# Main.net
KiCad netlist of a schematic drawn in Altium Designer
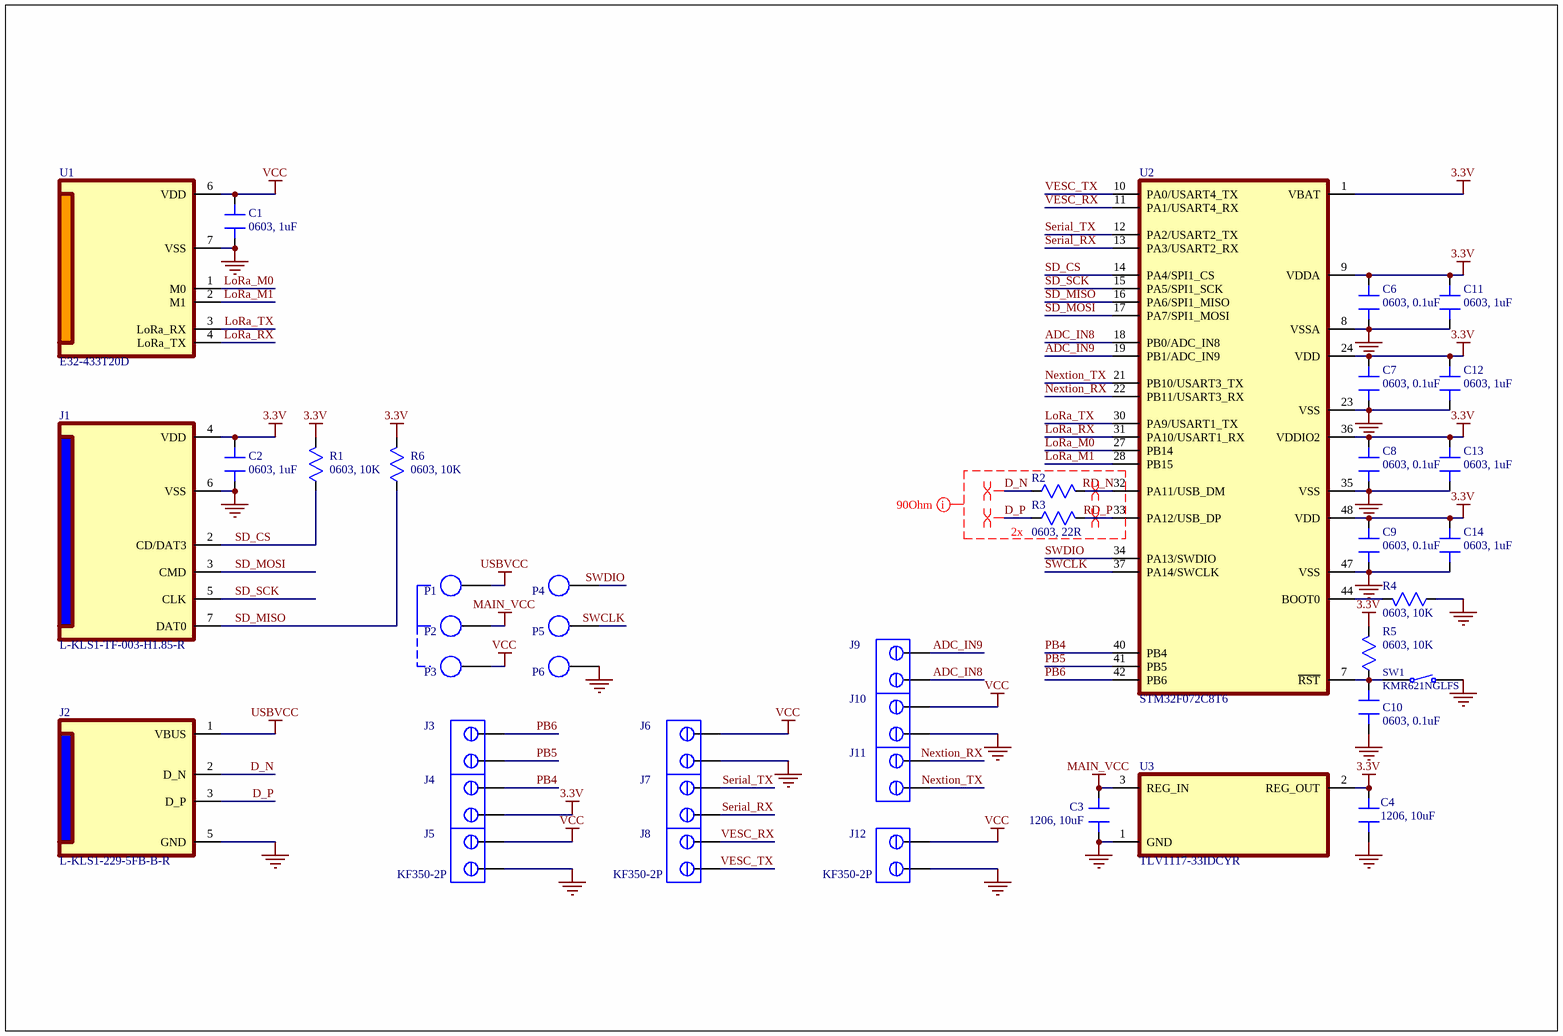
[diagram p0: Main.SchDoc]

(export (version "E")
  (design (tool "Eeschema 10.0.6"))
  (components
    (comp (ref "C1")
      (value "0603, 1uF")
      (footprint "CAP 0603_1608")
      (libsource (lib "Passives") (part "0603 Kapasitör"))
    )
    (comp (ref "C2")
      (value "0603, 1uF")
      (footprint "CAP 0603_1608")
      (libsource (lib "Passives") (part "0603 Kapasitör"))
    )
    (comp (ref "C3")
      (value "1206, 10uF")
      (footprint "CAP 1206_3216")
      (libsource (lib "Passives") (part "1206 Kapasitör"))
    )
    (comp (ref "C4")
      (value "1206, 10uF")
      (footprint "CAP 1206_3216")
      (libsource (lib "Passives") (part "1206 Kapasitör"))
    )
    (comp (ref "C6")
      (value "0603, 0.1uF")
      (footprint "CAP 0603_1608")
      (libsource (lib "Passives") (part "0603 Kapasitör"))
    )
    (comp (ref "C7")
      (value "0603, 0.1uF")
      (footprint "CAP 0603_1608")
      (libsource (lib "Passives") (part "0603 Kapasitör"))
    )
    (comp (ref "C8")
      (value "0603, 0.1uF")
      (footprint "CAP 0603_1608")
      (libsource (lib "Passives") (part "0603 Kapasitör"))
    )
    (comp (ref "C9")
      (value "0603, 0.1uF")
      (footprint "CAP 0603_1608")
      (libsource (lib "Passives") (part "0603 Kapasitör"))
    )
    (comp (ref "C10")
      (value "0603, 0.1uF")
      (footprint "CAP 0603_1608")
      (libsource (lib "Passives") (part "0603 Kapasitör"))
    )
    (comp (ref "C11")
      (value "0603, 1uF")
      (footprint "CAP 0603_1608")
      (libsource (lib "Passives") (part "0603 Kapasitör"))
    )
    (comp (ref "C12")
      (value "0603, 1uF")
      (footprint "CAP 0603_1608")
      (libsource (lib "Passives") (part "0603 Kapasitör"))
    )
    (comp (ref "C13")
      (value "0603, 1uF")
      (footprint "CAP 0603_1608")
      (libsource (lib "Passives") (part "0603 Kapasitör"))
    )
    (comp (ref "C14")
      (value "0603, 1uF")
      (footprint "CAP 0603_1608")
      (libsource (lib "Passives") (part "0603 Kapasitör"))
    )
    (comp (ref "J1")
      (value "L-KLS1-TF-003-H1.85-R")
      (footprint "L-KLS1-TF-003-H1.85-R")
      (libsource (lib "L-KLS1-TF-003-H1.85-R") (part "L-KLS1-TF-003-H1.85-R"))
    )
    (comp (ref "J2")
      (value "L-KLS1-229-5FB-B-R")
      (footprint "L-KLS1-229-5FB-B-R")
      (libsource (lib "L-KLS1-229-5FB-B-R") (part "L-KLS1-229-5FB-B-R"))
    )
    (comp (ref "J3") (value "KF350-2P") (footprint "KF350-2P") (libsource (lib "KF350") (part "KF350-2P")))
    (comp (ref "J4") (value "KF350-2P") (footprint "KF350-2P") (libsource (lib "KF350") (part "KF350-2P")))
    (comp (ref "J5") (value "KF350-2P") (footprint "KF350-2P") (libsource (lib "KF350") (part "KF350-2P")))
    (comp (ref "J6") (value "KF350-2P") (footprint "KF350-2P") (libsource (lib "KF350") (part "KF350-2P")))
    (comp (ref "J7") (value "KF350-2P") (footprint "KF350-2P") (libsource (lib "KF350") (part "KF350-2P")))
    (comp (ref "J8") (value "KF350-2P") (footprint "KF350-2P") (libsource (lib "KF350") (part "KF350-2P")))
    (comp (ref "J9") (value "KF350-2P") (footprint "KF350-2P") (libsource (lib "KF350") (part "KF350-2P")))
    (comp (ref "J10") (value "KF350-2P") (footprint "KF350-2P") (libsource (lib "KF350") (part "KF350-2P")))
    (comp (ref "J11") (value "KF350-2P") (footprint "KF350-2P") (libsource (lib "KF350") (part "KF350-2P")))
    (comp (ref "J12") (value "KF350-2P") (footprint "KF350-2P") (libsource (lib "KF350") (part "KF350-2P")))
    (comp (ref "P1") (value "Pad") (footprint "PAD") (libsource (lib "Passives") (part "Pad")))
    (comp (ref "P2") (value "Pad") (footprint "PAD") (libsource (lib "Passives") (part "Pad")))
    (comp (ref "P3") (value "Pad") (footprint "PAD") (libsource (lib "Passives") (part "Pad")))
    (comp (ref "P4") (value "Pad") (footprint "PAD") (libsource (lib "Passives") (part "Pad")))
    (comp (ref "P5") (value "Pad") (footprint "PAD") (libsource (lib "Passives") (part "Pad")))
    (comp (ref "P6") (value "Pad") (footprint "PAD") (libsource (lib "Passives") (part "Pad")))
    (comp (ref "R1")
      (value "0603, 10K")
      (footprint "RES 0603_1608")
      (libsource (lib "Passives") (part "0603 Direnç"))
    )
    (comp (ref "R2")
      (value "0603, ?R/K")
      (footprint "RES 0603_1608")
      (libsource (lib "Passives") (part "0603 Direnç"))
    )
    (comp (ref "R3")
      (value "0603, 22R")
      (footprint "RES 0603_1608")
      (libsource (lib "Passives") (part "0603 Direnç"))
    )
    (comp (ref "R4")
      (value "0603, 10K")
      (footprint "RES 0603_1608")
      (libsource (lib "Passives") (part "0603 Direnç"))
    )
    (comp (ref "R5")
      (value "0603, 10K")
      (footprint "RES 0603_1608")
      (libsource (lib "Passives") (part "0603 Direnç"))
    )
    (comp (ref "R6")
      (value "0603, 10K")
      (footprint "RES 0603_1608")
      (libsource (lib "Passives") (part "0603 Direnç"))
    )
    (comp (ref "SW1")
      (value "KMR621NGLFS")
      (footprint "SW_KMR621NGLFS")
      (libsource (lib "KMR621NGLFS") (part "KMR621NGLFS"))
    )
    (comp (ref "U1")
      (value "E32-433T20D")
      (footprint "E32-433T20D")
      (libsource (lib "E32-433T20D") (part "E32-433T20D"))
    )
    (comp (ref "U2")
      (value "STM32F072C8T6")
      (footprint "STM32F072C8T6")
      (libsource (lib "STM32F072C8T6") (part "STM32F072C8T6"))
    )
    (comp (ref "U3")
      (value "TLV1117-33IDCYR")
      (footprint "SOT230P700X180-4N")
      (libsource (lib "TLV1117-33IDCYR") (part "TLV1117-33IDCYR"))
    )
  )
  (nets
    (net (code "1") (name "/ADC_IN8") (class "Default")
      (node (ref "J9") (pin "2") (pinfunction "2_2") (pintype "passive"))
      (node (ref "U2") (pin "18") (pinfunction "PB0/ADC_IN8_18") (pintype "passive"))
    )
    (net (code "2") (name "/ADC_IN9") (class "Default")
      (node (ref "J9") (pin "1") (pinfunction "1_1") (pintype "passive"))
      (node (ref "U2") (pin "19") (pinfunction "PB1/ADC_IN9_19") (pintype "passive"))
    )
    (net (code "3") (name "/D_N") (class "Default")
      (node (ref "J2") (pin "2") (pinfunction "D_N_2") (pintype "passive"))
      (node (ref "R2") (pin "2") (pinfunction "2_2") (pintype "passive"))
    )
    (net (code "4") (name "/D_P") (class "Default")
      (node (ref "J2") (pin "3") (pinfunction "D_P_3") (pintype "passive"))
      (node (ref "R3") (pin "2") (pinfunction "2_2") (pintype "passive"))
    )
    (net (code "5") (name "/LoRa_M0") (class "Default")
      (node (ref "U1") (pin "1") (pinfunction "M0_1") (pintype "passive"))
      (node (ref "U2") (pin "27") (pinfunction "PB14_27") (pintype "passive"))
    )
    (net (code "6") (name "/LoRa_M1") (class "Default")
      (node (ref "U1") (pin "2") (pinfunction "M1_2") (pintype "passive"))
      (node (ref "U2") (pin "28") (pinfunction "PB15_28") (pintype "passive"))
    )
    (net (code "7") (name "/LoRa_RX") (class "Default")
      (node (ref "U1") (pin "4") (pinfunction "LoRa_TX_4") (pintype "passive"))
      (node (ref "U2") (pin "31") (pinfunction "PA10/USART1_RX_31") (pintype "passive"))
    )
    (net (code "8") (name "/LoRa_TX") (class "Default")
      (node (ref "U1") (pin "3") (pinfunction "LoRa_RX_3") (pintype "passive"))
      (node (ref "U2") (pin "30") (pinfunction "PA9/USART1_TX_30") (pintype "passive"))
    )
    (net (code "9") (name "/Nextion_RX") (class "Default")
      (node (ref "J11") (pin "1") (pinfunction "1_1") (pintype "passive"))
      (node (ref "U2") (pin "22") (pinfunction "PB11/USART3_RX_22") (pintype "passive"))
    )
    (net (code "10") (name "/Nextion_TX") (class "Default")
      (node (ref "J11") (pin "2") (pinfunction "2_2") (pintype "passive"))
      (node (ref "U2") (pin "21") (pinfunction "PB10/USART3_TX_21") (pintype "passive"))
    )
    (net (code "11") (name "/PB4") (class "Default")
      (node (ref "J4") (pin "1") (pinfunction "1_1") (pintype "passive"))
      (node (ref "U2") (pin "40") (pinfunction "PB4_40") (pintype "passive"))
    )
    (net (code "12") (name "/PB5") (class "Default")
      (node (ref "J3") (pin "2") (pinfunction "2_2") (pintype "passive"))
      (node (ref "U2") (pin "41") (pinfunction "PB5_41") (pintype "passive"))
    )
    (net (code "13") (name "/PB6") (class "Default")
      (node (ref "J3") (pin "1") (pinfunction "1_1") (pintype "passive"))
      (node (ref "U2") (pin "42") (pinfunction "PB6_42") (pintype "passive"))
    )
    (net (code "14") (name "/RD_N") (class "Default")
      (node (ref "R2") (pin "1") (pinfunction "1_1") (pintype "passive"))
      (node (ref "U2") (pin "32") (pinfunction "PA11/USB_DM_32") (pintype "passive"))
    )
    (net (code "15") (name "/RD_P") (class "Default")
      (node (ref "R3") (pin "1") (pinfunction "1_1") (pintype "passive"))
      (node (ref "U2") (pin "33") (pinfunction "PA12/USB_DP_33") (pintype "passive"))
    )
    (net (code "16") (name "/SD_CS") (class "Default")
      (node (ref "J1") (pin "2") (pinfunction "CD/DAT3_2") (pintype "passive"))
      (node (ref "R1") (pin "2") (pinfunction "2_2") (pintype "passive"))
      (node (ref "U2") (pin "14") (pinfunction "PA4/SPI1_CS_14") (pintype "passive"))
    )
    (net (code "17") (name "/SD_MISO") (class "Default")
      (node (ref "J1") (pin "7") (pinfunction "DAT0_7") (pintype "passive"))
      (node (ref "R6") (pin "2") (pinfunction "2_2") (pintype "passive"))
      (node (ref "U2") (pin "16") (pinfunction "PA6/SPI1_MISO_16") (pintype "passive"))
    )
    (net (code "18") (name "/SD_MOSI") (class "Default")
      (node (ref "J1") (pin "3") (pinfunction "CMD_3") (pintype "passive"))
      (node (ref "U2") (pin "17") (pinfunction "PA7/SPI1_MOSI_17") (pintype "passive"))
    )
    (net (code "19") (name "/SD_SCK") (class "Default")
      (node (ref "J1") (pin "5") (pinfunction "CLK_5") (pintype "passive"))
      (node (ref "U2") (pin "15") (pinfunction "PA5/SPI1_SCK_15") (pintype "passive"))
    )
    (net (code "20") (name "/SWCLK") (class "Default")
      (node (ref "P5") (pin "1") (pinfunction "1_1") (pintype "passive"))
      (node (ref "U2") (pin "37") (pinfunction "PA14/SWCLK_37") (pintype "passive"))
    )
    (net (code "21") (name "/SWDIO") (class "Default")
      (node (ref "P4") (pin "1") (pinfunction "1_1") (pintype "passive"))
      (node (ref "U2") (pin "34") (pinfunction "PA13/SWDIO_34") (pintype "passive"))
    )
    (net (code "22") (name "/Serial_RX") (class "Default")
      (node (ref "J7") (pin "2") (pinfunction "2_2") (pintype "passive"))
      (node (ref "U2") (pin "13") (pinfunction "PA3/USART2_RX_13") (pintype "passive"))
    )
    (net (code "23") (name "/Serial_TX") (class "Default")
      (node (ref "J7") (pin "1") (pinfunction "1_1") (pintype "passive"))
      (node (ref "U2") (pin "12") (pinfunction "PA2/USART2_TX_12") (pintype "passive"))
    )
    (net (code "24") (name "/VESC_RX") (class "Default")
      (node (ref "J8") (pin "1") (pinfunction "1_1") (pintype "passive"))
      (node (ref "U2") (pin "11") (pinfunction "PA1/USART4_RX_11") (pintype "passive"))
    )
    (net (code "25") (name "/VESC_TX") (class "Default")
      (node (ref "J8") (pin "2") (pinfunction "2_2") (pintype "passive"))
      (node (ref "U2") (pin "10") (pinfunction "PA0/USART4_TX_10") (pintype "passive"))
    )
    (net (code "26") (name "3.3V") (class "Default")
      (node (ref "C11") (pin "2") (pinfunction "2_2") (pintype "passive"))
      (node (ref "C12") (pin "2") (pinfunction "2_2") (pintype "passive"))
      (node (ref "C13") (pin "2") (pinfunction "2_2") (pintype "passive"))
      (node (ref "C14") (pin "2") (pinfunction "2_2") (pintype "passive"))
      (node (ref "C2") (pin "2") (pinfunction "2_2") (pintype "passive"))
      (node (ref "C4") (pin "2") (pinfunction "2_2") (pintype "passive"))
      (node (ref "C6") (pin "2") (pinfunction "2_2") (pintype "passive"))
      (node (ref "C7") (pin "2") (pinfunction "2_2") (pintype "passive"))
      (node (ref "C8") (pin "2") (pinfunction "2_2") (pintype "passive"))
      (node (ref "C9") (pin "2") (pinfunction "2_2") (pintype "passive"))
      (node (ref "J1") (pin "4") (pinfunction "VDD_4") (pintype "passive"))
      (node (ref "J4") (pin "2") (pinfunction "2_2") (pintype "passive"))
      (node (ref "R1") (pin "1") (pinfunction "1_1") (pintype "passive"))
      (node (ref "R5") (pin "1") (pinfunction "1_1") (pintype "passive"))
      (node (ref "R6") (pin "1") (pinfunction "1_1") (pintype "passive"))
      (node (ref "U2") (pin "1") (pinfunction "VBAT_1") (pintype "passive"))
      (node (ref "U2") (pin "24") (pinfunction "VDD_24") (pintype "passive"))
      (node (ref "U2") (pin "36") (pinfunction "VDDIO2_36") (pintype "passive"))
      (node (ref "U2") (pin "48") (pinfunction "VDD_48") (pintype "passive"))
      (node (ref "U2") (pin "9") (pinfunction "VDDA_9") (pintype "passive"))
      (node (ref "U3") (pin "2") (pinfunction "REG_OUT_2") (pintype "passive"))
    )
    (net (code "27") (name "GND") (class "Default")
      (node (ref "C1") (pin "1") (pinfunction "1_1") (pintype "passive"))
      (node (ref "C10") (pin "1") (pinfunction "1_1") (pintype "passive"))
      (node (ref "C11") (pin "1") (pinfunction "1_1") (pintype "passive"))
      (node (ref "C12") (pin "1") (pinfunction "1_1") (pintype "passive"))
      (node (ref "C13") (pin "1") (pinfunction "1_1") (pintype "passive"))
      (node (ref "C14") (pin "1") (pinfunction "1_1") (pintype "passive"))
      (node (ref "C2") (pin "1") (pinfunction "1_1") (pintype "passive"))
      (node (ref "C3") (pin "1") (pinfunction "1_1") (pintype "passive"))
      (node (ref "C4") (pin "1") (pinfunction "1_1") (pintype "passive"))
      (node (ref "C6") (pin "1") (pinfunction "1_1") (pintype "passive"))
      (node (ref "C7") (pin "1") (pinfunction "1_1") (pintype "passive"))
      (node (ref "C8") (pin "1") (pinfunction "1_1") (pintype "passive"))
      (node (ref "C9") (pin "1") (pinfunction "1_1") (pintype "passive"))
      (node (ref "J1") (pin "6") (pinfunction "VSS_6") (pintype "passive"))
      (node (ref "J10") (pin "2") (pinfunction "2_2") (pintype "passive"))
      (node (ref "J12") (pin "2") (pinfunction "2_2") (pintype "passive"))
      (node (ref "J2") (pin "5") (pinfunction "GND_5") (pintype "passive"))
      (node (ref "J5") (pin "2") (pinfunction "2_2") (pintype "passive"))
      (node (ref "J6") (pin "2") (pinfunction "2_2") (pintype "passive"))
      (node (ref "P6") (pin "1") (pinfunction "1_1") (pintype "passive"))
      (node (ref "R4") (pin "2") (pinfunction "2_2") (pintype "passive"))
      (node (ref "SW1") (pin "1") (pinfunction "1_1") (pintype "passive"))
      (node (ref "U1") (pin "7") (pinfunction "VSS_7") (pintype "passive"))
      (node (ref "U2") (pin "23") (pinfunction "VSS_23") (pintype "passive"))
      (node (ref "U2") (pin "35") (pinfunction "VSS_35") (pintype "passive"))
      (node (ref "U2") (pin "47") (pinfunction "VSS_47") (pintype "passive"))
      (node (ref "U2") (pin "8") (pinfunction "VSSA_8") (pintype "passive"))
      (node (ref "U3") (pin "1") (pinfunction "GND_1") (pintype "passive"))
    )
    (net (code "28") (name "MAIN_VCC") (class "Default")
      (node (ref "C3") (pin "2") (pinfunction "2_2") (pintype "passive"))
      (node (ref "P2") (pin "1") (pinfunction "1_1") (pintype "passive"))
      (node (ref "U3") (pin "3") (pinfunction "REG_IN_3") (pintype "passive"))
    )
    (net (code "29") (name "Net-(U2-BOOT0)") (class "Default")
      (node (ref "R4") (pin "1") (pinfunction "1_1") (pintype "passive"))
      (node (ref "U2") (pin "44") (pinfunction "BOOT0_44") (pintype "passive"))
    )
    (net (code "30") (name "Net-(U2-~{RST})") (class "Default")
      (node (ref "C10") (pin "2") (pinfunction "2_2") (pintype "passive"))
      (node (ref "R5") (pin "2") (pinfunction "2_2") (pintype "passive"))
      (node (ref "SW1") (pin "2") (pinfunction "2_2") (pintype "passive"))
      (node (ref "U2") (pin "7") (pinfunction "~{RST}_7") (pintype "passive"))
    )
    (net (code "31") (name "USBVCC") (class "Default")
      (node (ref "J2") (pin "1") (pinfunction "VBUS_1") (pintype "passive"))
      (node (ref "P1") (pin "1") (pinfunction "1_1") (pintype "passive"))
    )
    (net (code "32") (name "VCC") (class "Default")
      (node (ref "C1") (pin "2") (pinfunction "2_2") (pintype "passive"))
      (node (ref "J10") (pin "1") (pinfunction "1_1") (pintype "passive"))
      (node (ref "J12") (pin "1") (pinfunction "1_1") (pintype "passive"))
      (node (ref "J5") (pin "1") (pinfunction "1_1") (pintype "passive"))
      (node (ref "J6") (pin "1") (pinfunction "1_1") (pintype "passive"))
      (node (ref "P3") (pin "1") (pinfunction "1_1") (pintype "passive"))
      (node (ref "U1") (pin "6") (pinfunction "VDD_6") (pintype "passive"))
    )
  )
)
